# cn3704.net
KiCad netlist of a schematic drawn in EAGLE
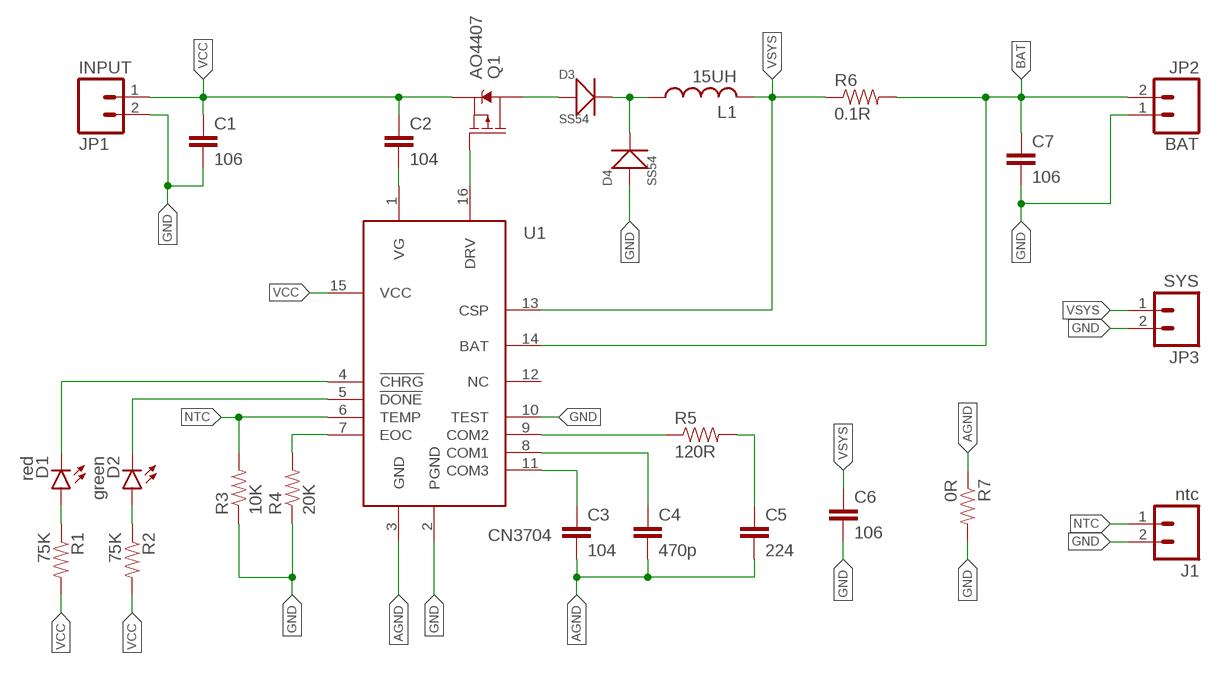
[diagram p0: schematic, sheet 1]

(export (version "E")
  (design (tool "Eeschema 10.0.6"))
  (components
    (comp (ref "C1")
      (value "106")
      (footprint "eagle-import:1206")
      (libsource (lib "eagle-import") (part "CAP1206"))
    )
    (comp (ref "C2")
      (value "104")
      (footprint "eagle-import:0603-CAP")
      (libsource (lib "eagle-import") (part "CAP0603-CAP"))
    )
    (comp (ref "C3")
      (value "104")
      (footprint "eagle-import:C0402")
      (libsource (lib "eagle-import") (part "CAP-SEEED-0402"))
    )
    (comp (ref "C4")
      (value "470p")
      (footprint "eagle-import:C0402")
      (libsource (lib "eagle-import") (part "CAP-SEEED-0402"))
    )
    (comp (ref "C5")
      (value "224")
      (footprint "eagle-import:C0402")
      (libsource (lib "eagle-import") (part "CAP-SEEED-0402"))
    )
    (comp (ref "C6")
      (value "106")
      (footprint "eagle-import:1206")
      (libsource (lib "eagle-import") (part "CAP1206"))
    )
    (comp (ref "C7")
      (value "106")
      (footprint "eagle-import:1206")
      (libsource (lib "eagle-import") (part "CAP1206"))
    )
    (comp (ref "D1")
      (value "red")
      (footprint "eagle-import:LED-0603-SEEED")
      (libsource (lib "eagle-import") (part "LED-SEEED-0603"))
    )
    (comp (ref "D2")
      (value "green")
      (footprint "eagle-import:LED-0603-SEEED")
      (libsource (lib "eagle-import") (part "LED-SEEED-0603"))
    )
    (comp (ref "D3")
      (value "SS54")
      (footprint "eagle-import:DO-214AB")
      (fields (field (name "MPN") "SS34-E3/57T"))
      (libsource (lib "eagle-import") (part "SMD-DIODE-SCHOTTKY-40V-3A(DO-214AB)"))
    )
    (comp (ref "D4")
      (value "SS54")
      (footprint "eagle-import:DO-214AC")
      (fields (field (name "MPN") "1N5819"))
      (libsource (lib "eagle-import") (part "SMD-DIODE-SCHOTTKY-40V-1A(DO-214AC)"))
    )
    (comp (ref "J1")
      (value "ntc")
      (footprint "eagle-import:1X02_NO_SILK")
      (libsource (lib "eagle-import") (part "M021X02_NO_SILK"))
    )
    (comp (ref "JP1")
      (value "INPUT")
      (footprint "eagle-import:SCREWTERMINAL-5MM-2")
      (libsource (lib "eagle-import") (part "xmgu2008_M025MM"))
    )
    (comp (ref "JP2")
      (value "BAT")
      (footprint "eagle-import:SCREWTERMINAL-5MM-2")
      (libsource (lib "eagle-import") (part "xmgu2008_M025MM"))
    )
    (comp (ref "JP3")
      (value "SYS")
      (footprint "eagle-import:SCREWTERMINAL-5MM-2")
      (libsource (lib "eagle-import") (part "xmgu2008_M025MM"))
    )
    (comp (ref "L1")
      (value "15UH")
      (footprint "eagle-import:L_SMDRI-127")
      (libsource (lib "eagle-import") (part "L-SMDRI-127"))
    )
    (comp (ref "Q1")
      (value "AO4407")
      (footprint "eagle-import:SO08")
      (libsource (lib "eagle-import") (part "MOSFET_PCH-NDS8434"))
    )
    (comp (ref "R1")
      (value "75K")
      (footprint "eagle-import:R0402")
      (libsource (lib "eagle-import") (part "RESISTOR-SEEED-0402"))
    )
    (comp (ref "R2")
      (value "75K")
      (footprint "eagle-import:R0402")
      (libsource (lib "eagle-import") (part "RESISTOR-SEEED-0402"))
    )
    (comp (ref "R3")
      (value "10K")
      (footprint "eagle-import:R0402")
      (libsource (lib "eagle-import") (part "RESISTOR-SEEED-0402"))
    )
    (comp (ref "R4")
      (value "20K")
      (footprint "eagle-import:R0402")
      (libsource (lib "eagle-import") (part "RESISTOR-SEEED-0402"))
    )
    (comp (ref "R5")
      (value "120R")
      (footprint "eagle-import:R0402")
      (libsource (lib "eagle-import") (part "RESISTOR-SEEED-0402"))
    )
    (comp (ref "R6")
      (value "0.1R")
      (footprint "eagle-import:R2512")
      (libsource (lib "eagle-import") (part "RESISTOR2512"))
    )
    (comp (ref "R7")
      (value "0R")
      (footprint "eagle-import:R0402")
      (libsource (lib "eagle-import") (part "RESISTOR-SEEED-0402"))
    )
    (comp (ref "U1")
      (value "CN3704")
      (footprint "eagle-import:TSSOP16")
      (libsource (lib "eagle-import") (part "CN3702"))
    )
  )
  (nets
    (net (code "1") (name "AGND") (class "Default")
      (node (ref "C3") (pin "2") (pinfunction "2_2") (pintype "passive"))
      (node (ref "C4") (pin "2") (pinfunction "2_2") (pintype "passive"))
      (node (ref "C5") (pin "2") (pinfunction "2_2") (pintype "passive"))
      (node (ref "R7") (pin "1") (pinfunction "1_1") (pintype "passive"))
      (node (ref "U1") (pin "3") (pinfunction "GND_3") (pintype "bidirectional"))
    )
    (net (code "2") (name "BAT") (class "Default")
      (node (ref "C7") (pin "1") (pinfunction "1_1") (pintype "passive"))
      (node (ref "JP2") (pin "2") (pinfunction "2_2") (pintype "passive"))
      (node (ref "R6") (pin "2") (pinfunction "2_2") (pintype "passive"))
      (node (ref "U1") (pin "14") (pinfunction "BAT_14") (pintype "bidirectional"))
    )
    (net (code "3") (name "GND") (class "Default")
      (node (ref "C1") (pin "2") (pinfunction "2_2") (pintype "passive"))
      (node (ref "C6") (pin "2") (pinfunction "2_2") (pintype "passive"))
      (node (ref "C7") (pin "2") (pinfunction "2_2") (pintype "passive"))
      (node (ref "D4") (pin "1") (pinfunction "+_1") (pintype "passive"))
      (node (ref "J1") (pin "2") (pinfunction "2_2") (pintype "passive"))
      (node (ref "JP1") (pin "2") (pinfunction "2_2") (pintype "passive"))
      (node (ref "JP2") (pin "1") (pinfunction "1_1") (pintype "passive"))
      (node (ref "JP3") (pin "2") (pinfunction "2_2") (pintype "passive"))
      (node (ref "R3") (pin "1") (pinfunction "1_1") (pintype "passive"))
      (node (ref "R4") (pin "1") (pinfunction "1_1") (pintype "passive"))
      (node (ref "R7") (pin "2") (pinfunction "2_2") (pintype "passive"))
      (node (ref "U1") (pin "10") (pinfunction "TEST_10") (pintype "bidirectional"))
      (node (ref "U1") (pin "2") (pinfunction "PGND_2") (pintype "bidirectional"))
    )
    (net (code "4") (name "NTC") (class "Default")
      (node (ref "J1") (pin "1") (pinfunction "1_1") (pintype "passive"))
      (node (ref "R3") (pin "2") (pinfunction "2_2") (pintype "passive"))
      (node (ref "U1") (pin "6") (pinfunction "TEMP_6") (pintype "bidirectional"))
    )
    (net (code "5") (name "Net-(C5-Pad1)") (class "Default")
      (node (ref "C5") (pin "1") (pinfunction "1_1") (pintype "passive"))
      (node (ref "R5") (pin "2") (pinfunction "2_2") (pintype "passive"))
    )
    (net (code "6") (name "Net-(D1-A)") (class "Default")
      (node (ref "D1") (pin "+") (pinfunction "A_+") (pintype "passive"))
      (node (ref "R1") (pin "1") (pinfunction "1_1") (pintype "passive"))
    )
    (net (code "7") (name "Net-(D1-C)") (class "Default")
      (node (ref "D1") (pin "-") (pinfunction "C_-") (pintype "passive"))
      (node (ref "U1") (pin "4") (pinfunction "~{CHRG}_4") (pintype "bidirectional"))
    )
    (net (code "8") (name "Net-(D2-A)") (class "Default")
      (node (ref "D2") (pin "+") (pinfunction "A_+") (pintype "passive"))
      (node (ref "R2") (pin "1") (pinfunction "1_1") (pintype "passive"))
    )
    (net (code "9") (name "Net-(D2-C)") (class "Default")
      (node (ref "D2") (pin "-") (pinfunction "C_-") (pintype "passive"))
      (node (ref "U1") (pin "5") (pinfunction "~{DONE}_5") (pintype "bidirectional"))
    )
    (net (code "10") (name "Net-(D3-+)") (class "Default")
      (node (ref "D3") (pin "1") (pinfunction "+_1") (pintype "passive"))
      (node (ref "Q1") (pin "5") (pinfunction "D_5") (pintype "bidirectional"))
      (node (ref "Q1") (pin "6") (pinfunction "D_6") (pintype "bidirectional"))
      (node (ref "Q1") (pin "7") (pinfunction "D_7") (pintype "bidirectional"))
      (node (ref "Q1") (pin "8") (pinfunction "D_8") (pintype "bidirectional"))
    )
    (net (code "11") (name "Net-(D3--)") (class "Default")
      (node (ref "D3") (pin "2") (pinfunction "-_2") (pintype "passive"))
      (node (ref "D4") (pin "2") (pinfunction "-_2") (pintype "passive"))
      (node (ref "L1") (pin "1") (pinfunction "1_1") (pintype "passive"))
    )
    (net (code "12") (name "Net-(Q1-G)") (class "Default")
      (node (ref "Q1") (pin "4") (pinfunction "G_4") (pintype "bidirectional"))
      (node (ref "U1") (pin "16") (pinfunction "DRV_16") (pintype "bidirectional"))
    )
    (net (code "13") (name "Net-(U1-COM1)") (class "Default")
      (node (ref "C4") (pin "1") (pinfunction "1_1") (pintype "passive"))
      (node (ref "U1") (pin "8") (pinfunction "COM1_8") (pintype "bidirectional"))
    )
    (net (code "14") (name "Net-(U1-COM2)") (class "Default")
      (node (ref "R5") (pin "1") (pinfunction "1_1") (pintype "passive"))
      (node (ref "U1") (pin "9") (pinfunction "COM2_9") (pintype "bidirectional"))
    )
    (net (code "15") (name "Net-(U1-COM3)") (class "Default")
      (node (ref "C3") (pin "1") (pinfunction "1_1") (pintype "passive"))
      (node (ref "U1") (pin "11") (pinfunction "COM3_11") (pintype "bidirectional"))
    )
    (net (code "16") (name "Net-(U1-EOC)") (class "Default")
      (node (ref "R4") (pin "2") (pinfunction "2_2") (pintype "passive"))
      (node (ref "U1") (pin "7") (pinfunction "EOC_7") (pintype "bidirectional"))
    )
    (net (code "17") (name "Net-(U1-VG)") (class "Default")
      (node (ref "C2") (pin "2") (pinfunction "2_2") (pintype "passive"))
      (node (ref "U1") (pin "1") (pinfunction "VG_1") (pintype "bidirectional"))
    )
    (net (code "18") (name "VCC") (class "Default")
      (node (ref "C1") (pin "1") (pinfunction "1_1") (pintype "passive"))
      (node (ref "C2") (pin "1") (pinfunction "1_1") (pintype "passive"))
      (node (ref "JP1") (pin "1") (pinfunction "1_1") (pintype "passive"))
      (node (ref "Q1") (pin "1") (pinfunction "S_1") (pintype "bidirectional"))
      (node (ref "Q1") (pin "2") (pinfunction "S_2") (pintype "bidirectional"))
      (node (ref "Q1") (pin "3") (pinfunction "S_3") (pintype "bidirectional"))
      (node (ref "R1") (pin "2") (pinfunction "2_2") (pintype "passive"))
      (node (ref "R2") (pin "2") (pinfunction "2_2") (pintype "passive"))
      (node (ref "U1") (pin "15") (pinfunction "VCC_15") (pintype "bidirectional"))
    )
    (net (code "19") (name "VSYS") (class "Default")
      (node (ref "C6") (pin "1") (pinfunction "1_1") (pintype "passive"))
      (node (ref "JP3") (pin "1") (pinfunction "1_1") (pintype "passive"))
      (node (ref "L1") (pin "2") (pinfunction "2_2") (pintype "passive"))
      (node (ref "R6") (pin "1") (pinfunction "1_1") (pintype "passive"))
      (node (ref "U1") (pin "13") (pinfunction "CSP_13") (pintype "bidirectional"))
    )
    (net (code "20") (name "unconnected-(U1-NC-Pad12)") (class "Default")
      (node (ref "U1") (pin "12") (pinfunction "NC_12") (pintype "bidirectional"))
    )
  )
)
